# esrmeter.net
KiCad netlist of a schematic drawn in EAGLE
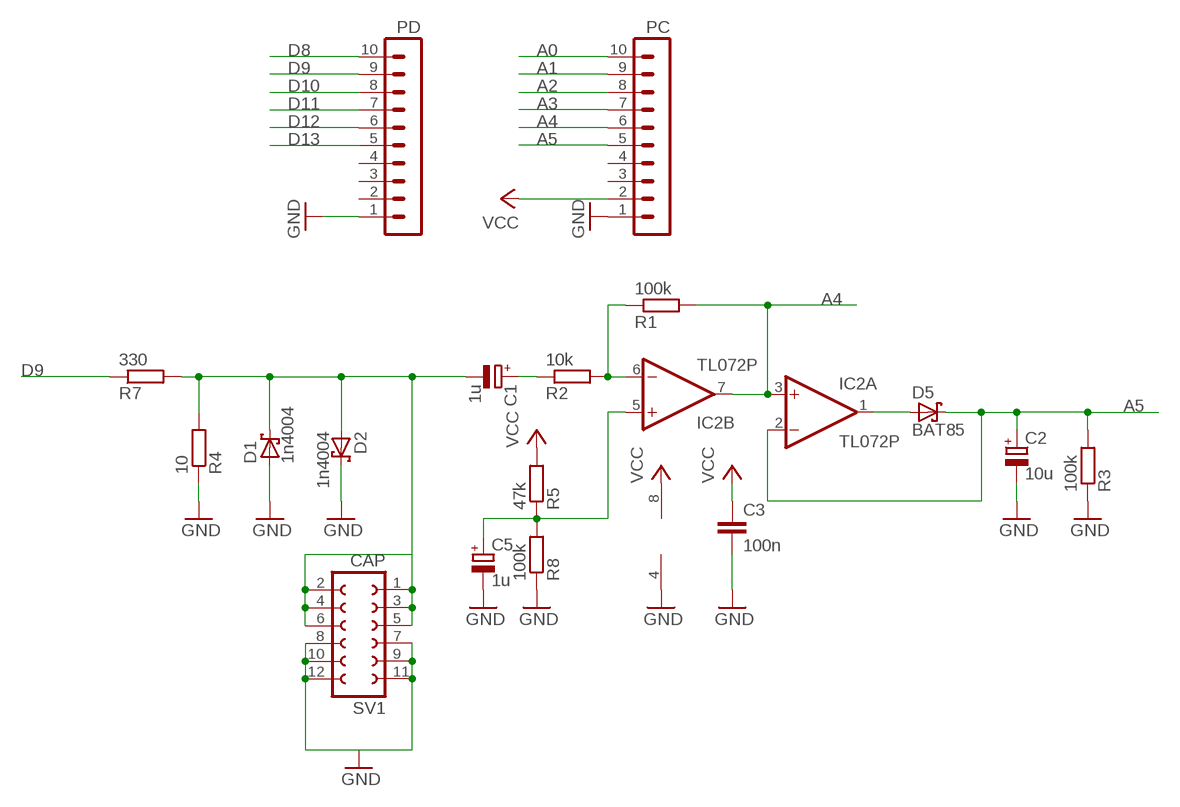
[diagram p0: schematic, sheet 1]

(export (version "E")
  (design (tool "Eeschema 10.0.6"))
  (components
    (comp (ref "C1")
      (value "1u")
      (footprint "eagle-import:TT2D6")
      (libsource (lib "eagle-import") (part "CPOL-EUTT2D6"))
    )
    (comp (ref "C2")
      (value "10u")
      (footprint "eagle-import:TT5D7")
      (libsource (lib "eagle-import") (part "CPOL-EUTT5D7"))
    )
    (comp (ref "C3")
      (value "100n")
      (footprint "eagle-import:C025-024X044")
      (libsource (lib "eagle-import") (part "C-EU025-024X044"))
    )
    (comp (ref "C5")
      (value "1u")
      (footprint "eagle-import:TT5D7")
      (libsource (lib "eagle-import") (part "CPOL-EUTT5D7"))
    )
    (comp (ref "D1")
      (value "1n4004")
      (footprint "eagle-import:TO92H")
      (libsource (lib "eagle-import") (part "SCHOTTKY-DIODETO92H"))
    )
    (comp (ref "D2")
      (value "1n4004")
      (footprint "eagle-import:TO92H")
      (libsource (lib "eagle-import") (part "SCHOTTKY-DIODETO92H"))
    )
    (comp (ref "D5")
      (value "BAT85")
      (footprint "eagle-import:TO92H")
      (libsource (lib "eagle-import") (part "SCHOTTKY-DIODETO92H"))
    )
    (comp (ref "IC2")
      (value "TL072P")
      (footprint "eagle-import:DIL08")
      (libsource (lib "eagle-import") (part "TL072P"))
    )
    (comp (ref "PC")
      (value "MA10-1W")
      (footprint "eagle-import:MA10-1W")
      (libsource (lib "eagle-import") (part "MA10-1W"))
    )
    (comp (ref "PD")
      (value "MA10-1W")
      (footprint "eagle-import:MA10-1W")
      (libsource (lib "eagle-import") (part "MA10-1W"))
    )
    (comp (ref "R1")
      (value "100k")
      (footprint "eagle-import:0207_2V")
      (libsource (lib "eagle-import") (part "R-EU_0207/2V"))
    )
    (comp (ref "R2")
      (value "10k")
      (footprint "eagle-import:0617_17")
      (libsource (lib "eagle-import") (part "R-EU_0617/17"))
    )
    (comp (ref "R3")
      (value "100k")
      (footprint "eagle-import:0207_10")
      (libsource (lib "eagle-import") (part "R-EU_0207/10"))
    )
    (comp (ref "R4")
      (value "10")
      (footprint "eagle-import:0207_2V")
      (libsource (lib "eagle-import") (part "R-EU_0207/2V"))
    )
    (comp (ref "R5")
      (value "47k")
      (footprint "eagle-import:0207_2V")
      (libsource (lib "eagle-import") (part "R-EU_0207/2V"))
    )
    (comp (ref "R7")
      (value "330")
      (footprint "eagle-import:0617_22")
      (libsource (lib "eagle-import") (part "R-EU_0617/22"))
    )
    (comp (ref "R8")
      (value "100k")
      (footprint "eagle-import:0204_5")
      (libsource (lib "eagle-import") (part "R-EU_0204/5"))
    )
    (comp (ref "SV1")
      (value "CAP")
      (footprint "eagle-import:FE06-2W")
      (libsource (lib "eagle-import") (part "FE06-2W"))
    )
  )
  (nets
    (net (code "1") (name "/A0") (class "Default")
      (node (ref "PC") (pin "10") (pinfunction "10_10") (pintype "passive"))
    )
    (net (code "2") (name "/A1") (class "Default")
      (node (ref "PC") (pin "9") (pinfunction "9_9") (pintype "passive"))
    )
    (net (code "3") (name "/A2") (class "Default")
      (node (ref "PC") (pin "8") (pinfunction "8_8") (pintype "passive"))
    )
    (net (code "4") (name "/A3") (class "Default")
      (node (ref "PC") (pin "7") (pinfunction "7_7") (pintype "passive"))
    )
    (net (code "5") (name "/A4") (class "Default")
      (node (ref "IC2") (pin "3") (pinfunction "+IN_3") (pintype "input"))
      (node (ref "IC2") (pin "7") (pinfunction "OUT_7") (pintype "output"))
      (node (ref "PC") (pin "6") (pinfunction "6_6") (pintype "passive"))
      (node (ref "R1") (pin "2") (pinfunction "2_2") (pintype "passive"))
    )
    (net (code "6") (name "/A5") (class "Default")
      (node (ref "C2") (pin "+") (pinfunction "+_+") (pintype "passive"))
      (node (ref "D5") (pin "2") (pinfunction "C_2") (pintype "passive"))
      (node (ref "IC2") (pin "2") (pinfunction "-IN_2") (pintype "input"))
      (node (ref "PC") (pin "5") (pinfunction "5_5") (pintype "passive"))
      (node (ref "R3") (pin "2") (pinfunction "2_2") (pintype "passive"))
    )
    (net (code "7") (name "/D8") (class "Default")
      (node (ref "PD") (pin "10") (pinfunction "10_10") (pintype "passive"))
    )
    (net (code "8") (name "/D9") (class "Default")
      (node (ref "PD") (pin "9") (pinfunction "9_9") (pintype "passive"))
      (node (ref "R7") (pin "1") (pinfunction "1_1") (pintype "passive"))
    )
    (net (code "9") (name "/D10") (class "Default")
      (node (ref "PD") (pin "8") (pinfunction "8_8") (pintype "passive"))
    )
    (net (code "10") (name "/D11") (class "Default")
      (node (ref "PD") (pin "7") (pinfunction "7_7") (pintype "passive"))
    )
    (net (code "11") (name "/D12") (class "Default")
      (node (ref "PD") (pin "6") (pinfunction "6_6") (pintype "passive"))
    )
    (net (code "12") (name "/D13") (class "Default")
      (node (ref "PD") (pin "5") (pinfunction "5_5") (pintype "passive"))
    )
    (net (code "13") (name "GND") (class "Default")
      (node (ref "C2") (pin "-") (pinfunction "-_-") (pintype "passive"))
      (node (ref "C3") (pin "2") (pinfunction "2_2") (pintype "passive"))
      (node (ref "C5") (pin "-") (pinfunction "-_-") (pintype "passive"))
      (node (ref "D1") (pin "1") (pinfunction "A_1") (pintype "passive"))
      (node (ref "D2") (pin "2") (pinfunction "C_2") (pintype "passive"))
      (node (ref "IC2") (pin "4") (pinfunction "V-_4") (pintype "power_in"))
      (node (ref "PC") (pin "1") (pinfunction "1_1") (pintype "passive"))
      (node (ref "PD") (pin "1") (pinfunction "1_1") (pintype "passive"))
      (node (ref "R3") (pin "1") (pinfunction "1_1") (pintype "passive"))
      (node (ref "R4") (pin "1") (pinfunction "1_1") (pintype "passive"))
      (node (ref "R8") (pin "1") (pinfunction "1_1") (pintype "passive"))
      (node (ref "SV1") (pin "10") (pinfunction "10_10") (pintype "passive"))
      (node (ref "SV1") (pin "11") (pinfunction "11_11") (pintype "passive"))
      (node (ref "SV1") (pin "12") (pinfunction "12_12") (pintype "passive"))
      (node (ref "SV1") (pin "7") (pinfunction "7_7") (pintype "passive"))
      (node (ref "SV1") (pin "8") (pinfunction "8_8") (pintype "passive"))
      (node (ref "SV1") (pin "9") (pinfunction "9_9") (pintype "passive"))
    )
    (net (code "14") (name "Net-(C1-Pad+)") (class "Default")
      (node (ref "C1") (pin "+") (pinfunction "+_+") (pintype "passive"))
      (node (ref "R2") (pin "1") (pinfunction "1_1") (pintype "passive"))
    )
    (net (code "15") (name "Net-(D1-C)") (class "Default")
      (node (ref "C1") (pin "-") (pinfunction "-_-") (pintype "passive"))
      (node (ref "D1") (pin "2") (pinfunction "C_2") (pintype "passive"))
      (node (ref "D2") (pin "1") (pinfunction "A_1") (pintype "passive"))
      (node (ref "R4") (pin "2") (pinfunction "2_2") (pintype "passive"))
      (node (ref "R7") (pin "2") (pinfunction "2_2") (pintype "passive"))
      (node (ref "SV1") (pin "1") (pinfunction "1_1") (pintype "passive"))
      (node (ref "SV1") (pin "2") (pinfunction "2_2") (pintype "passive"))
      (node (ref "SV1") (pin "3") (pinfunction "3_3") (pintype "passive"))
      (node (ref "SV1") (pin "4") (pinfunction "4_4") (pintype "passive"))
      (node (ref "SV1") (pin "5") (pinfunction "5_5") (pintype "passive"))
      (node (ref "SV1") (pin "6") (pinfunction "6_6") (pintype "passive"))
    )
    (net (code "16") (name "Net-(D5-A)") (class "Default")
      (node (ref "D5") (pin "1") (pinfunction "A_1") (pintype "passive"))
      (node (ref "IC2") (pin "1") (pinfunction "OUT_1") (pintype "output"))
    )
    (net (code "17") (name "Net-(IC2B-+IN)") (class "Default")
      (node (ref "C5") (pin "+") (pinfunction "+_+") (pintype "passive"))
      (node (ref "IC2") (pin "5") (pinfunction "+IN_5") (pintype "input"))
      (node (ref "R5") (pin "1") (pinfunction "1_1") (pintype "passive"))
      (node (ref "R8") (pin "2") (pinfunction "2_2") (pintype "passive"))
    )
    (net (code "18") (name "Net-(IC2B--IN)") (class "Default")
      (node (ref "IC2") (pin "6") (pinfunction "-IN_6") (pintype "input"))
      (node (ref "R1") (pin "1") (pinfunction "1_1") (pintype "passive"))
      (node (ref "R2") (pin "2") (pinfunction "2_2") (pintype "passive"))
    )
    (net (code "19") (name "VCC") (class "Default")
      (node (ref "C3") (pin "1") (pinfunction "1_1") (pintype "passive"))
      (node (ref "IC2") (pin "8") (pinfunction "V+_8") (pintype "power_in"))
      (node (ref "PC") (pin "2") (pinfunction "2_2") (pintype "passive"))
      (node (ref "R5") (pin "2") (pinfunction "2_2") (pintype "passive"))
    )
    (net (code "20") (name "unconnected-(PC-Pad3)") (class "Default")
      (node (ref "PC") (pin "3") (pinfunction "3_3") (pintype "passive"))
    )
    (net (code "21") (name "unconnected-(PC-Pad4)") (class "Default")
      (node (ref "PC") (pin "4") (pinfunction "4_4") (pintype "passive"))
    )
    (net (code "22") (name "unconnected-(PD-Pad2)") (class "Default")
      (node (ref "PD") (pin "2") (pinfunction "2_2") (pintype "passive"))
    )
    (net (code "23") (name "unconnected-(PD-Pad3)") (class "Default")
      (node (ref "PD") (pin "3") (pinfunction "3_3") (pintype "passive"))
    )
    (net (code "24") (name "unconnected-(PD-Pad4)") (class "Default")
      (node (ref "PD") (pin "4") (pinfunction "4_4") (pintype "passive"))
    )
  )
)
